# Battery_Charger.net
KiCad netlist of a schematic drawn in Altium Designer
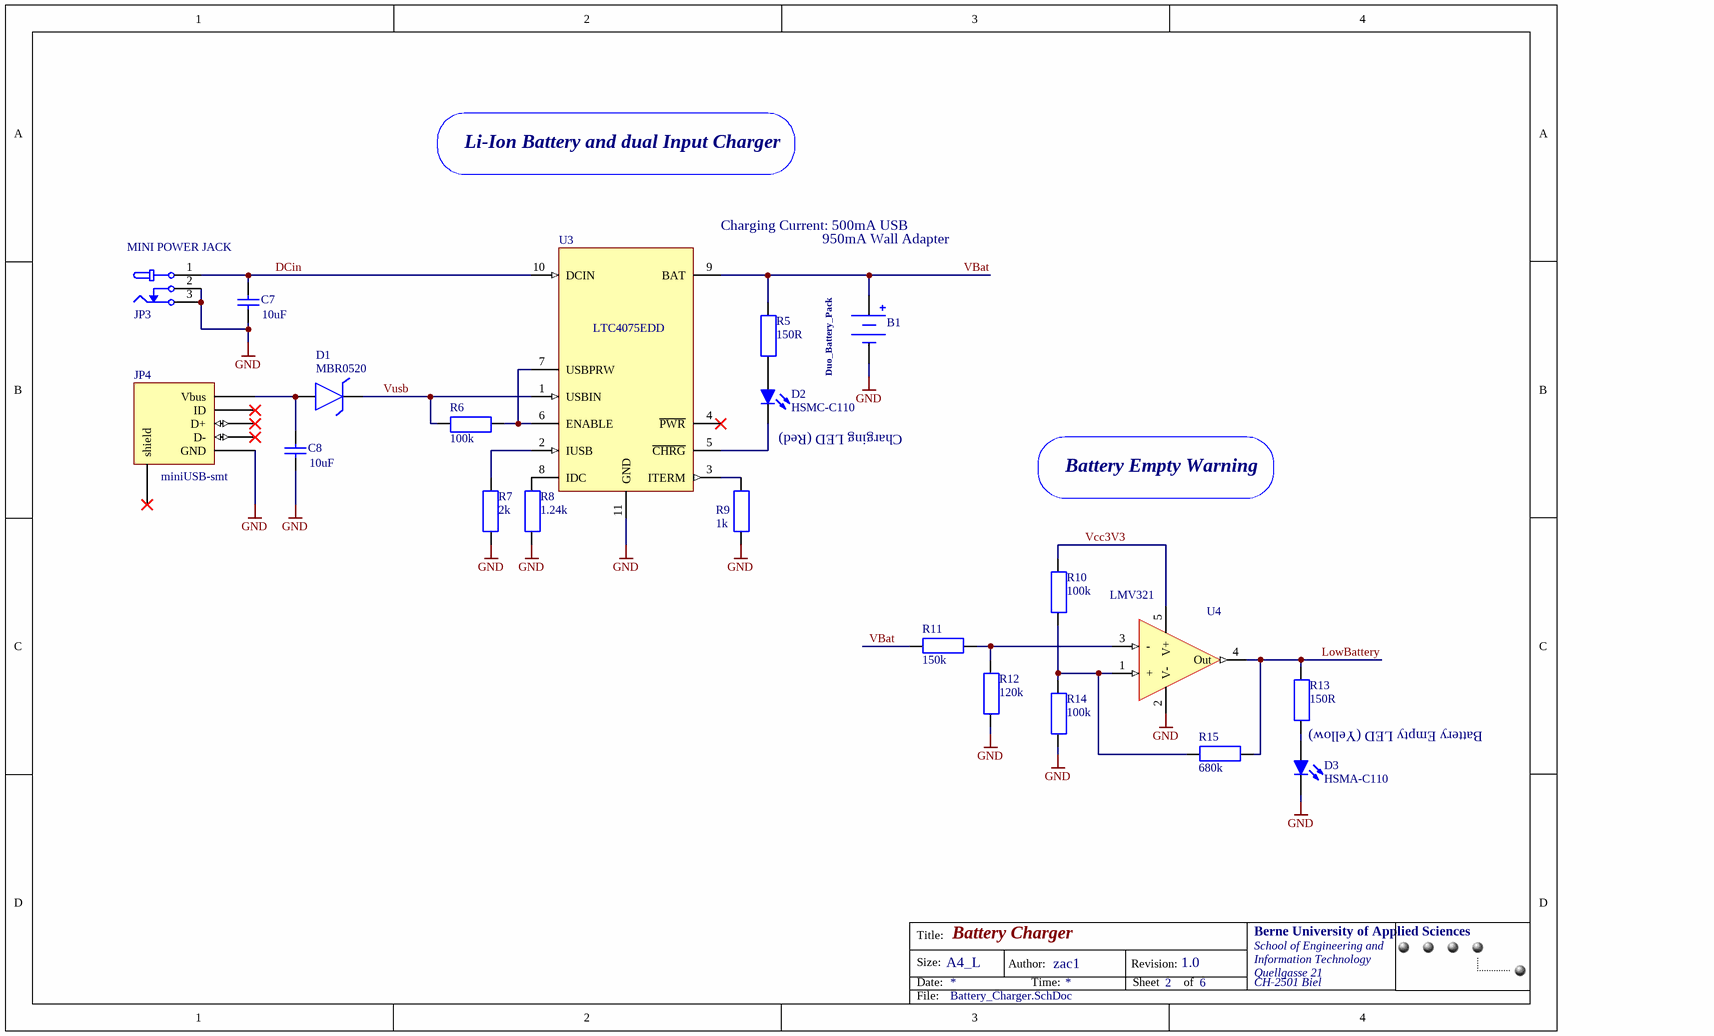
[diagram p0: Battery_Charger.SchDoc]

(export (version "E")
  (design (tool "Eeschema 10.0.6"))
  (components
    (comp (ref "B1")
      (value "New_Battery")
      (footprint "Battery_new")
      (fields (field (name "MANUFACTURER") "Contrel") (field (name "PART NUMBER") "PA-LP987"))
      (libsource (lib "Power_supply") (part "BATTERY_NEW"))
    )
    (comp (ref "C7")
      (value "10uF")
      (footprint "C1206")
      (description "Capacitor (Semiconductor SIM Model)")
      (fields
        (field (name "MANUFACTURER") "Murata")
        (field (name "PART NUMBER") "GRM31CR70J106KA01L")
        (field (name "PUBLISHER") "Altium Limited")
      )
      (libsource (lib "Miscellaneous Devices") (part "Cap Semi"))
    )
    (comp (ref "C8")
      (value "10uF")
      (footprint "C1206")
      (description "Capacitor (Semiconductor SIM Model)")
      (fields
        (field (name "MANUFACTURER") "Murata")
        (field (name "PART NUMBER") "GRM31CR70J106KA01L")
        (field (name "PUBLISHER") "Altium Limited")
      )
      (libsource (lib "Miscellaneous Devices") (part "Cap Semi"))
    )
    (comp (ref "D1")
      (value "MBR0520")
      (footprint "sod-123")
      (fields
        (field (name "PART TYPE") "MBR0520")
        (field (name "MANUFACTURER") "ON Semi")
        (field (name "PART NUMBER") "MBR0520LT1G")
      )
      (libsource (lib "Power_supply") (part "SCHOTTKY_MBR05*"))
    )
    (comp (ref "D2")
      (value "HSMC-C110")
      (footprint "HSMC-C110")
      (description "LED")
      (fields (field (name "PART TYPE") "HSMC-C110") (field (name "MANUFACTURER") "Avago"))
      (libsource (lib "Power_supply") (part "LED-HSM*-C110"))
    )
    (comp (ref "D3")
      (value "HSMA-C110")
      (footprint "HSMC-C110")
      (description "LED")
      (fields (field (name "PART TYPE") "HSMA-C110") (field (name "MANUFACTURER") "Avago"))
      (libsource (lib "Power_supply") (part "LED-HSM*-C110"))
    )
    (comp (ref "JP3")
      (value "MINI POWER JACK")
      (footprint "Mini power Jack")
      (description "Mini Power Jack")
      (fields (field (name "MANUFACTURER") "CLIFF ELECTRONIC") (field (name "PART NUMBER") "DC8"))
      (libsource (lib "Power_supply_library") (part "MINI POWER JACK"))
    )
    (comp (ref "JP4")
      (value "miniUSB-smt")
      (footprint "USB_MINI_B_SMD")
      (fields
        (field (name "MANUFACTURER") "Lumberg")
        (field (name "PART NUMBER") "2486 01")
        (field (name "Comment") "USB-MINIB-SMT")
      )
      (libsource (lib "gecko3-user") (part "USB-MINIB-SMT"))
    )
    (comp (ref "R5")
      (value "150R")
      (footprint "1608[0603]")
      (description "Resistance")
      (fields
        (field (name "PART TYPE") "150R")
        (field (name "MANUFACTURER") "Multicomp")
        (field (name "PART NUMBER") "MC 0.063W 0603 1% 150R")
      )
      (libsource (lib "POWER_SUPPLY") (part "RES"))
    )
    (comp (ref "R6")
      (value "100k")
      (footprint "1608[0603]")
      (description "Resistance")
      (fields
        (field (name "PART TYPE") "100k")
        (field (name "MANUFACTURER") "Multicomp")
        (field (name "PART NUMBER") "MC 0.063W 0603 1% 100K")
      )
      (libsource (lib "POWER_SUPPLY") (part "RES"))
    )
    (comp (ref "R7")
      (value "2k")
      (footprint "1608[0603]")
      (description "Resistance")
      (fields
        (field (name "PART TYPE") "2k")
        (field (name "MANUFACTURER") "Multicomp")
        (field (name "PART NUMBER") "MC 0.063W 0603 1% 2K")
      )
      (libsource (lib "POWER_SUPPLY") (part "RES"))
    )
    (comp (ref "R8")
      (value "1.24k")
      (footprint "1608[0603]")
      (description "Resistance")
      (fields
        (field (name "PART TYPE") "1.24k")
        (field (name "MANUFACTURER") "Multicomp")
        (field (name "PART NUMBER") "MC 0.063W 0603 1% 1M")
      )
      (libsource (lib "POWER_SUPPLY") (part "RES"))
    )
    (comp (ref "R9")
      (value "1k")
      (footprint "1608[0603]")
      (description "Resistance")
      (fields
        (field (name "PART TYPE") "1k")
        (field (name "MANUFACTURER") "Multicomp")
        (field (name "PART NUMBER") "MC 0.063W 0603 1% 1K")
      )
      (libsource (lib "POWER_SUPPLY") (part "RES"))
    )
    (comp (ref "R10")
      (value "100k")
      (footprint "1608[0603]")
      (description "Resistance")
      (fields
        (field (name "PART TYPE") "100k")
        (field (name "MANUFACTURER") "Multicomp")
        (field (name "PART NUMBER") "MC 0.063W 0603 1% 100K")
      )
      (libsource (lib "POWER_SUPPLY") (part "RES"))
    )
    (comp (ref "R11")
      (value "150k")
      (footprint "1608[0603]")
      (description "Resistance")
      (fields
        (field (name "PART TYPE") "150k")
        (field (name "MANUFACTURER") "Multicomp")
        (field (name "PART NUMBER") "MC 0.063W 0603 1% 150K")
      )
      (libsource (lib "POWER_SUPPLY") (part "RES"))
    )
    (comp (ref "R12")
      (value "120k")
      (footprint "1608[0603]")
      (description "Resistance")
      (fields
        (field (name "PART TYPE") "120k")
        (field (name "MANUFACTURER") "Multicomp")
        (field (name "PART NUMBER") "MC 0.063W 0603 1% 120K")
      )
      (libsource (lib "POWER_SUPPLY") (part "RES"))
    )
    (comp (ref "R13")
      (value "150R")
      (footprint "1608[0603]")
      (description "Resistance")
      (fields
        (field (name "PART TYPE") "150R")
        (field (name "MANUFACTURER") "Multicomp")
        (field (name "PART NUMBER") "MC 0.063W 0603 1% 150R")
      )
      (libsource (lib "POWER_SUPPLY") (part "RES"))
    )
    (comp (ref "R14")
      (value "100k")
      (footprint "1608[0603]")
      (description "Resistance")
      (fields
        (field (name "PART TYPE") "100k")
        (field (name "MANUFACTURER") "Multicomp")
        (field (name "PART NUMBER") "MC 0.063W 0603 1% 100K")
      )
      (libsource (lib "POWER_SUPPLY") (part "RES"))
    )
    (comp (ref "R15")
      (value "680k")
      (footprint "1608[0603]")
      (description "Resistance")
      (fields
        (field (name "PART TYPE") "680k")
        (field (name "MANUFACTURER") "Multicomp")
        (field (name "PART NUMBER") "MC 0.063W 0603 1% 680K")
      )
      (libsource (lib "POWER_SUPPLY") (part "RES"))
    )
    (comp (ref "U3")
      (value "LTC4075EDD")
      (footprint "LTC4075")
      (fields (field (name "MANUFACTURER") "Linear") (field (name "PART NUMBER") "LTC4075EDD#PBF"))
      (libsource (lib "Power_supply") (part "LTC4075"))
    )
    (comp (ref "U4")
      (value "LMV321")
      (footprint "LMV331")
      (description "Op. Amp.")
      (fields (field (name "MANUFACTURER") "TI") (field (name "PART NUMBER") "LMV321IDBVR"))
      (libsource (lib "Power_supply") (part "LMV321"))
    )
  )
  (nets
    (net (code "2") (name "/DCin") (class "Default")
      (node (ref "C7") (pin "2") (pinfunction "2_2") (pintype "passive"))
      (node (ref "JP3") (pin "1") (pinfunction "VDD_1") (pintype "power_in"))
      (node (ref "U3") (pin "10") (pinfunction "DCIN_10") (pintype "input"))
    )
    (net (code "3") (name "/LowBattery") (class "Default")
      (node (ref "R13") (pin "2") (pinfunction "J2_2") (pintype "passive"))
      (node (ref "R15") (pin "1") (pinfunction "J1_1") (pintype "passive"))
      (node (ref "U4") (pin "4") (pinfunction "Out_4") (pintype "output"))
    )
    (net (code "4") (name "/VBat") (class "Default")
      (node (ref "B1") (pin "1") (pinfunction "J1_1") (pintype "passive"))
      (node (ref "R11") (pin "2") (pinfunction "J2_2") (pintype "passive"))
      (node (ref "R5") (pin "2") (pinfunction "J2_2") (pintype "passive"))
      (node (ref "U3") (pin "9") (pinfunction "BAT_9") (pintype "passive"))
    )
    (net (code "5") (name "/Vcc3V3") (class "Default")
      (node (ref "R10") (pin "2") (pinfunction "J2_2") (pintype "passive"))
      (node (ref "U4") (pin "5") (pinfunction "V+_5") (pintype "power_in"))
    )
    (net (code "6") (name "/Vusb") (class "Default")
      (node (ref "D1") (pin "1") (pinfunction "Cathode_1") (pintype "passive"))
      (node (ref "R6") (pin "1") (pinfunction "J1_1") (pintype "passive"))
      (node (ref "U3") (pin "1") (pinfunction "USBIN_1") (pintype "input"))
    )
    (net (code "7") (name "GND") (class "Default")
      (node (ref "B1") (pin "2") (pinfunction "J2_2") (pintype "passive"))
      (node (ref "C7") (pin "1") (pinfunction "1_1") (pintype "passive"))
      (node (ref "C8") (pin "1") (pinfunction "1_1") (pintype "passive"))
      (node (ref "D3") (pin "1") (pinfunction "K_1") (pintype "passive"))
      (node (ref "JP3") (pin "2") (pinfunction "GND_2") (pintype "power_in"))
      (node (ref "JP3") (pin "3") (pinfunction "GND_3") (pintype "power_in"))
      (node (ref "JP4") (pin "GND") (pinfunction "GND_GND") (pintype "power_in"))
      (node (ref "R12") (pin "1") (pinfunction "J1_1") (pintype "passive"))
      (node (ref "R14") (pin "1") (pinfunction "J1_1") (pintype "passive"))
      (node (ref "R7") (pin "2") (pinfunction "J2_2") (pintype "passive"))
      (node (ref "R8") (pin "1") (pinfunction "J1_1") (pintype "passive"))
      (node (ref "R9") (pin "1") (pinfunction "J1_1") (pintype "passive"))
      (node (ref "U3") (pin "11") (pinfunction "GND_11") (pintype "passive"))
      (node (ref "U4") (pin "2") (pinfunction "V-_2") (pintype "power_in"))
    )
    (net (code "8") (name "Net-(D1-Anode)") (class "Default")
      (node (ref "C8") (pin "2") (pinfunction "2_2") (pintype "passive"))
      (node (ref "D1") (pin "2") (pinfunction "Anode_2") (pintype "passive"))
      (node (ref "JP4") (pin "Vbus") (pinfunction "Vbus_Vbus") (pintype "power_in"))
    )
    (net (code "9") (name "Net-(D2-A)") (class "Default")
      (node (ref "D2") (pin "2") (pinfunction "A_2") (pintype "passive"))
      (node (ref "R5") (pin "1") (pinfunction "J1_1") (pintype "passive"))
    )
    (net (code "10") (name "Net-(D2-K)") (class "Default")
      (node (ref "D2") (pin "1") (pinfunction "K_1") (pintype "passive"))
      (node (ref "U3") (pin "5") (pinfunction "~{CHRG}_5") (pintype "passive"))
    )
    (net (code "11") (name "Net-(D3-A)") (class "Default")
      (node (ref "D3") (pin "2") (pinfunction "A_2") (pintype "passive"))
      (node (ref "R13") (pin "1") (pinfunction "J1_1") (pintype "passive"))
    )
    (net (code "12") (name "Net-(R6-J2)") (class "Default")
      (node (ref "R6") (pin "2") (pinfunction "J2_2") (pintype "passive"))
      (node (ref "U3") (pin "6") (pinfunction "ENABLE_6") (pintype "passive"))
      (node (ref "U3") (pin "7") (pinfunction "USBPRW_7") (pintype "passive"))
    )
    (net (code "13") (name "Net-(R7-J1)") (class "Default")
      (node (ref "R7") (pin "1") (pinfunction "J1_1") (pintype "passive"))
      (node (ref "U3") (pin "2") (pinfunction "IUSB_2") (pintype "input"))
    )
    (net (code "14") (name "Net-(R8-J2)") (class "Default")
      (node (ref "R8") (pin "2") (pinfunction "J2_2") (pintype "passive"))
      (node (ref "U3") (pin "8") (pinfunction "IDC_8") (pintype "passive"))
    )
    (net (code "15") (name "Net-(R9-J2)") (class "Default")
      (node (ref "R9") (pin "2") (pinfunction "J2_2") (pintype "passive"))
      (node (ref "U3") (pin "3") (pinfunction "ITERM_3") (pintype "output"))
    )
    (net (code "16") (name "Net-(R10-J1)") (class "Default")
      (node (ref "R10") (pin "1") (pinfunction "J1_1") (pintype "passive"))
      (node (ref "R14") (pin "2") (pinfunction "J2_2") (pintype "passive"))
      (node (ref "R15") (pin "2") (pinfunction "J2_2") (pintype "passive"))
      (node (ref "U4") (pin "1") (pinfunction "+_1") (pintype "input"))
    )
    (net (code "17") (name "Net-(R11-J1)") (class "Default")
      (node (ref "R11") (pin "1") (pinfunction "J1_1") (pintype "passive"))
      (node (ref "R12") (pin "2") (pinfunction "J2_2") (pintype "passive"))
      (node (ref "U4") (pin "3") (pinfunction "-_3") (pintype "input"))
    )
    (net (code "18") (name "unconnected-(JP4-PadD+)") (class "Default")
      (node (ref "JP4") (pin "D+") (pinfunction "D+_D+") (pintype "bidirectional+no_connect"))
    )
    (net (code "19") (name "unconnected-(JP4-PadD-)") (class "Default")
      (node (ref "JP4") (pin "D-") (pinfunction "D-_D-") (pintype "bidirectional+no_connect"))
    )
    (net (code "20") (name "unconnected-(JP4-PadID)") (class "Default")
      (node (ref "JP4") (pin "ID") (pinfunction "ID_ID") (pintype "passive+no_connect"))
    )
    (net (code "21") (name "unconnected-(JP4-Padshield)") (class "Default")
      (node (ref "JP4") (pin "shield") (pinfunction "shield_shield") (pintype "passive+no_connect"))
    )
    (net (code "22") (name "unconnected-(U3-~{PWR}-Pad4)") (class "Default")
      (node (ref "U3") (pin "4") (pinfunction "~{PWR}_4") (pintype "passive+no_connect"))
    )
  )
)
